# 3-4_TDR.net
KiCad netlist of a schematic drawn in Altium Designer
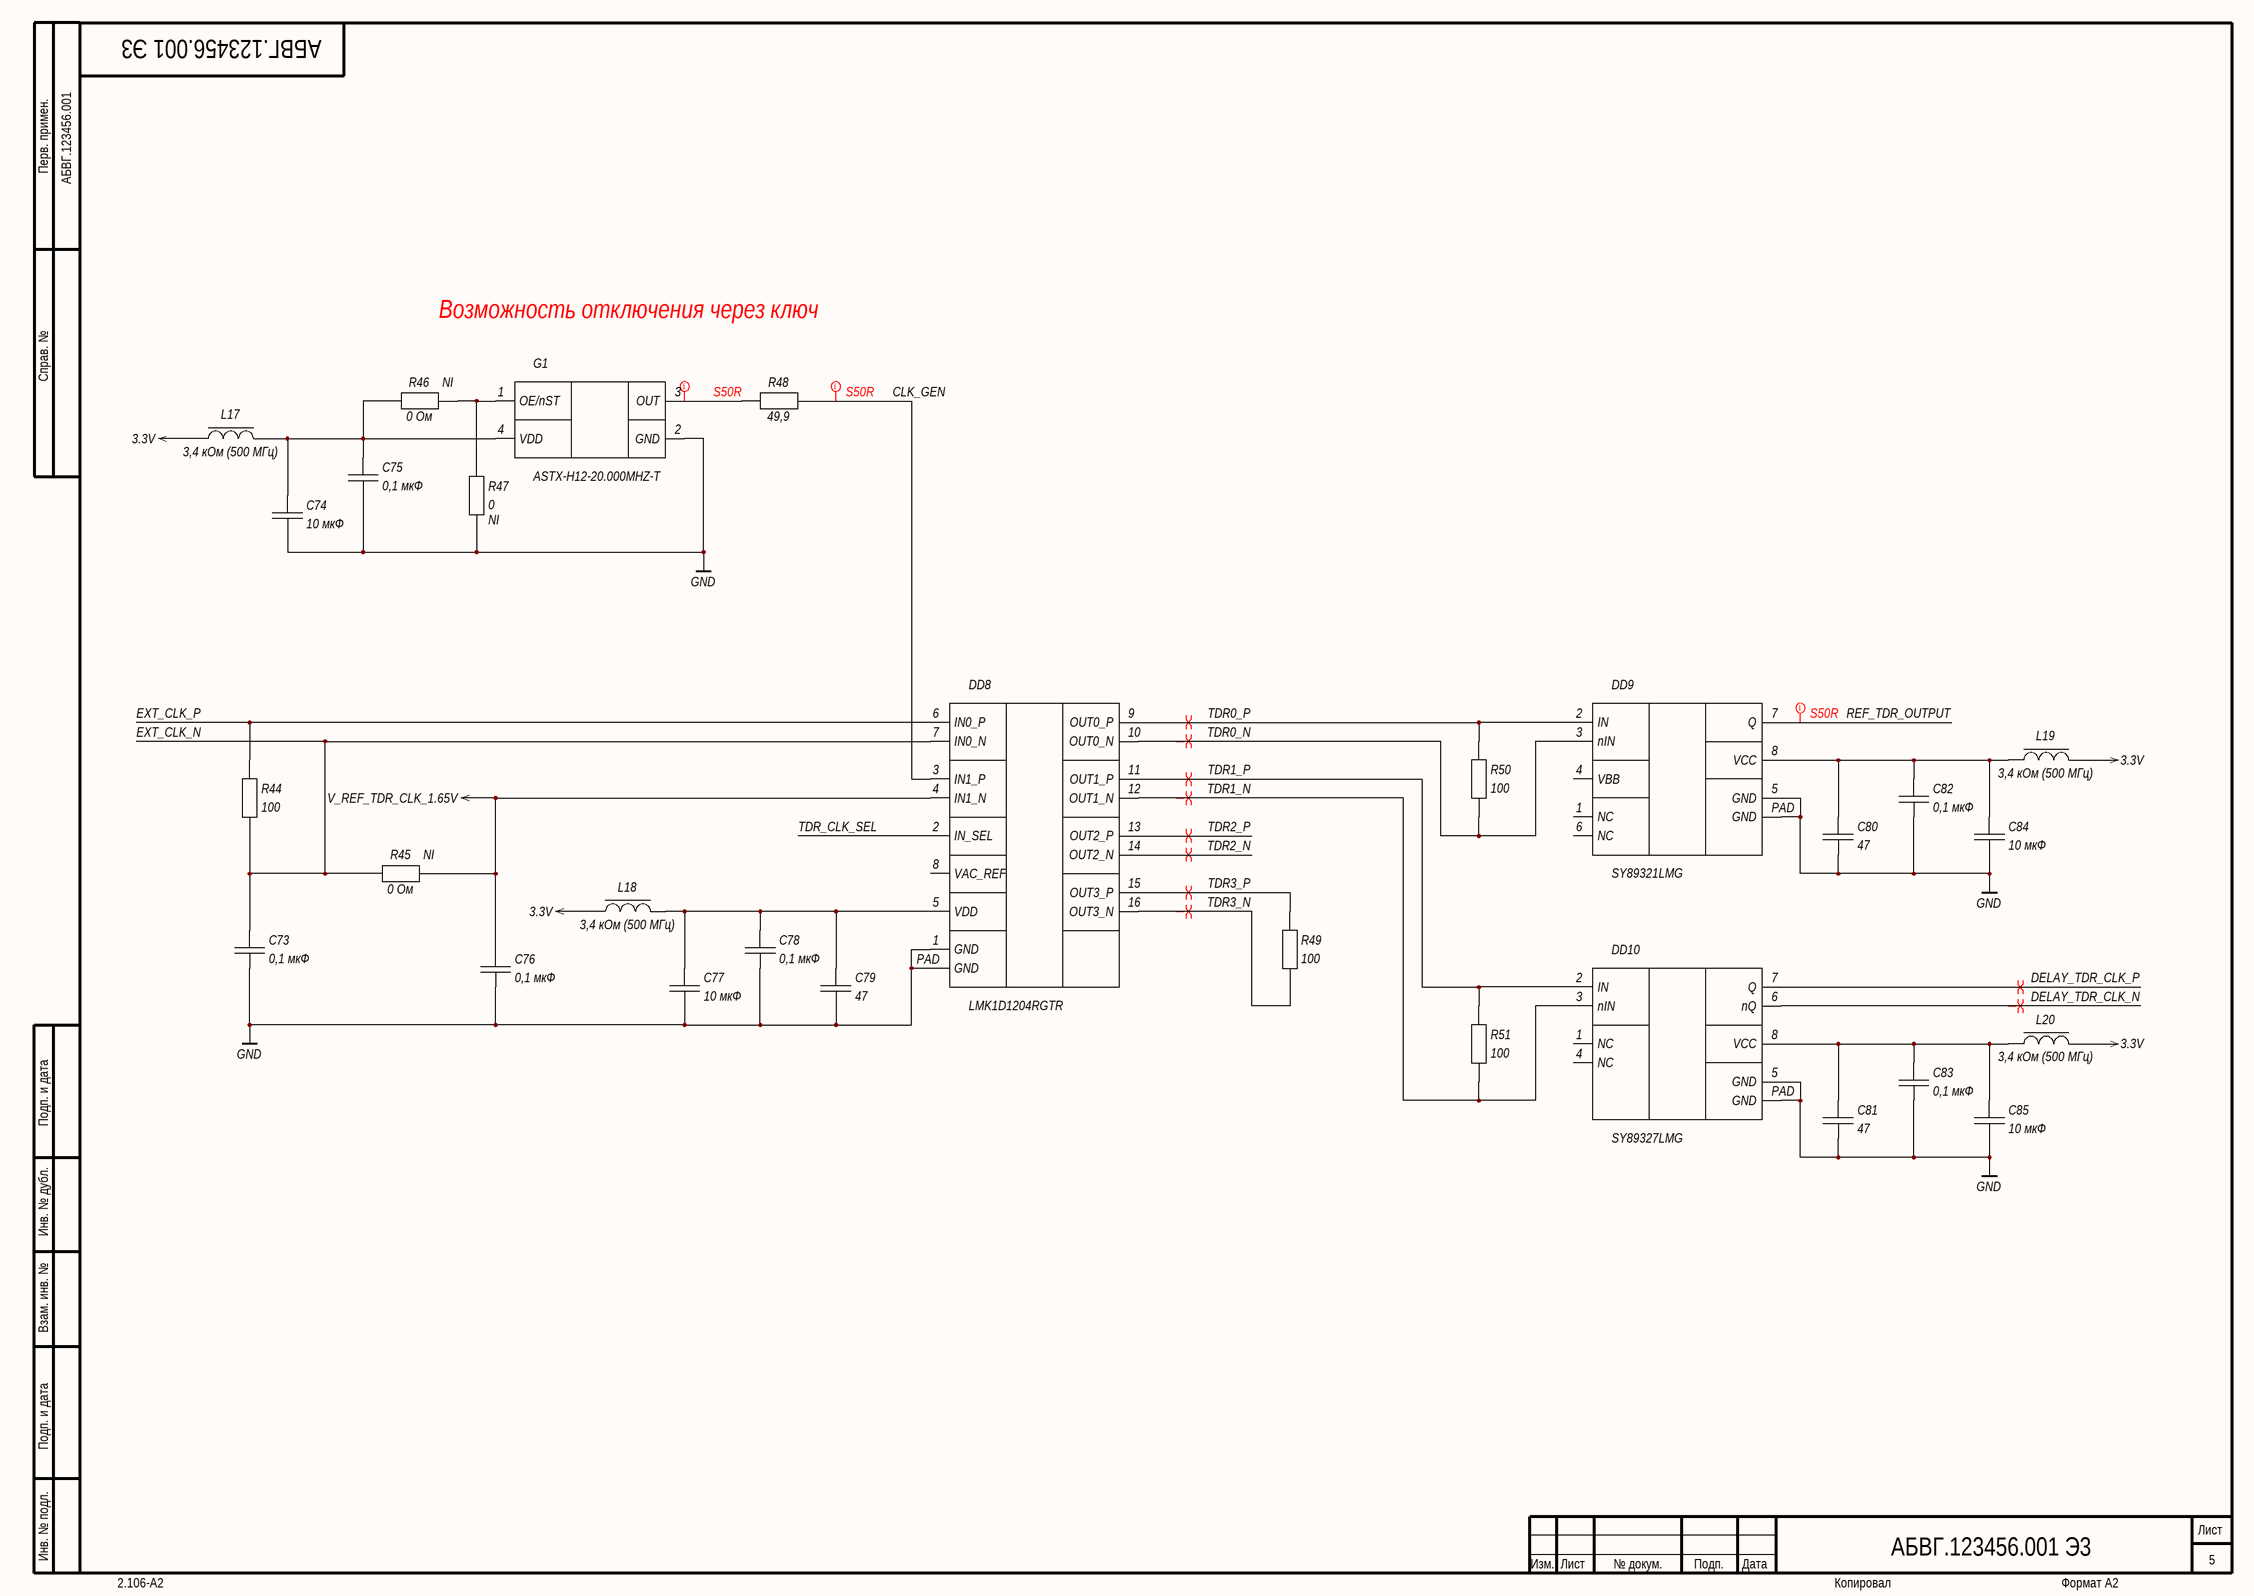
[diagram p0: Э3-4 TDR Делитель.SchDoc]

(export (version "E")
  (design (tool "Eeschema 10.0.6"))
  (components
    (comp (ref "C73")
      (value "0,1 мкФ")
      (footprint "C0402-B-0.5mm")
      (description "0402 X7R 0,1 мкФ ±10 % 50 В")
      (fields (field (name "PARTNUMBER") "GRM155R71H104KE14D"))
      (libsource (lib "Capacitors") (part "Non Polar Ver."))
    )
    (comp (ref "C74")
      (value "10 мкФ")
      (footprint "C0603-B-0.8mm")
      (description "0603 X5R 10 мкФ ±20 % 25 В")
      (fields (field (name "PARTNUMBER") "GRM188R61E106MA73"))
      (libsource (lib "Capacitors") (part "Non Polar Ver."))
    )
    (comp (ref "C75")
      (value "0,1 мкФ")
      (footprint "C0402-B-0.5mm")
      (description "0402 X7R 0,1 мкФ ±10 % 50 В")
      (fields (field (name "PARTNUMBER") "GRM155R71H104KE14D"))
      (libsource (lib "Capacitors") (part "Non Polar Ver."))
    )
    (comp (ref "C76")
      (value "0,1 мкФ")
      (footprint "C0402-B-0.5mm")
      (description "0402 X7R 0,1 мкФ ±10 % 50 В")
      (fields (field (name "PARTNUMBER") "GRM155R71H104KE14D"))
      (libsource (lib "Capacitors") (part "Non Polar Ver."))
    )
    (comp (ref "C77")
      (value "10 мкФ")
      (footprint "C0603-B-0.8mm")
      (description "0603 X5R 10 мкФ ±20 % 25 В")
      (fields (field (name "PARTNUMBER") "GRM188R61E106MA73"))
      (libsource (lib "Capacitors") (part "Non Polar Ver."))
    )
    (comp (ref "C78")
      (value "0,1 мкФ")
      (footprint "C0402-B-0.5mm")
      (description "0402 X7R 0,1 мкФ ±10 % 50 В")
      (fields (field (name "PARTNUMBER") "GRM155R71H104KE14D"))
      (libsource (lib "Capacitors") (part "Non Polar Ver."))
    )
    (comp (ref "C79")
      (value "47")
      (footprint "C0402-B-0.5mm")
      (description "0402 NP0 47 пФ ±5 % 50 В")
      (fields (field (name "PARTNUMBER") "GCM1555C1H470JA16"))
      (libsource (lib "Capacitors") (part "Non Polar Ver."))
    )
    (comp (ref "C80")
      (value "47")
      (footprint "C0402-B-0.5mm")
      (description "0402 NP0 47 пФ ±5 % 50 В")
      (fields (field (name "PARTNUMBER") "GCM1555C1H470JA16"))
      (libsource (lib "Capacitors") (part "Non Polar Ver."))
    )
    (comp (ref "C81")
      (value "47")
      (footprint "C0402-B-0.5mm")
      (description "0402 NP0 47 пФ ±5 % 50 В")
      (fields (field (name "PARTNUMBER") "GCM1555C1H470JA16"))
      (libsource (lib "Capacitors") (part "Non Polar Ver."))
    )
    (comp (ref "C82")
      (value "0,1 мкФ")
      (footprint "C0402-B-0.5mm")
      (description "0402 X7R 0,1 мкФ ±10 % 50 В")
      (fields (field (name "PARTNUMBER") "GRM155R71H104KE14D"))
      (libsource (lib "Capacitors") (part "Non Polar Ver."))
    )
    (comp (ref "C83")
      (value "0,1 мкФ")
      (footprint "C0402-B-0.5mm")
      (description "0402 X7R 0,1 мкФ ±10 % 50 В")
      (fields (field (name "PARTNUMBER") "GRM155R71H104KE14D"))
      (libsource (lib "Capacitors") (part "Non Polar Ver."))
    )
    (comp (ref "C84")
      (value "10 мкФ")
      (footprint "C0603-B-0.8mm")
      (description "0603 X5R 10 мкФ ±20 % 25 В")
      (fields (field (name "PARTNUMBER") "GRM188R61E106MA73"))
      (libsource (lib "Capacitors") (part "Non Polar Ver."))
    )
    (comp (ref "C85")
      (value "10 мкФ")
      (footprint "C0603-B-0.8mm")
      (description "0603 X5R 10 мкФ ±20 % 25 В")
      (fields (field (name "PARTNUMBER") "GRM188R61E106MA73"))
      (libsource (lib "Capacitors") (part "Non Polar Ver."))
    )
    (comp (ref "DD8")
      (value "LMK1D1204RGTR")
      (footprint "16-QFN-3-H1-EP1.7")
      (description "Low Additive Jitter LVDS Buffer")
      (fields (field (name "MANUFACTURER") "Texas Instruments, Inc."))
      (libsource (lib "Digital") (part "LMK1D1204"))
    )
    (comp (ref "DD9")
      (value "SY89321LMG")
      (footprint "8-MLF")
      (description "3.3V DIFFERENTIAL LVPECL/CML/LVDS-to-LVTTL TRANSLATOR")
      (fields (field (name "MANUFACTURER") "Microchip Technology"))
      (libsource (lib "Digital") (part "SY89321L"))
    )
    (comp (ref "DD10")
      (value "SY89327LMG")
      (footprint "8-MLF")
      (description "3.3V 2.5Gbps ANY INPUT-to-LVPECL DIFFERENTIAL TRANSLATOR")
      (fields (field (name "MANUFACTURER") "Microchip Technology"))
      (libsource (lib "Digital") (part "SY89327L"))
    )
    (comp (ref "G1")
      (value "ASTX-H12-20.000MHZ-T")
      (footprint "ASTX-H12")
      (fields (field (name "TOLERANCE") "± ppm"))
      (libsource (lib "Oscilators") (part "Generator"))
    )
    (comp (ref "L17")
      (value "3,4 кОм (500 МГц)")
      (footprint "L0402-B-0.5mm")
      (fields (field (name "PARTNUMBER") "BLM15HD182BH1"))
      (libsource (lib "Inductors") (part "Inductor MC Hor."))
    )
    (comp (ref "L18")
      (value "3,4 кОм (500 МГц)")
      (footprint "L0402-B-0.5mm")
      (fields (field (name "PARTNUMBER") "BLM15HD182BH1"))
      (libsource (lib "Inductors") (part "Inductor MC Hor."))
    )
    (comp (ref "L19")
      (value "3,4 кОм (500 МГц)")
      (footprint "L0402-B-0.5mm")
      (fields (field (name "PARTNUMBER") "BLM15HD182BH1"))
      (libsource (lib "Inductors") (part "Inductor MC Hor."))
    )
    (comp (ref "L20")
      (value "3,4 кОм (500 МГц)")
      (footprint "L0402-B-0.5mm")
      (fields (field (name "PARTNUMBER") "BLM15HD182BH1"))
      (libsource (lib "Inductors") (part "Inductor MC Hor."))
    )
    (comp (ref "R44")
      (value "100")
      (footprint "CR0402-B-0.35mm")
      (description "0402 100 Ом ±1 %")
      (libsource (lib "Resistors") (part "Resistor Ver."))
    )
    (comp (ref "R45")
      (value "0 Ом")
      (footprint "CR0402-B-0.35mm")
      (description "0402 0 Ом")
      (fields (field (name "COMPONENTTYPE") "NI"))
      (libsource (lib "Resistors") (part "Resistor Hor."))
    )
    (comp (ref "R46")
      (value "0 Ом")
      (footprint "CR0402-B-0.35mm")
      (description "0402 0 Ом")
      (fields (field (name "COMPONENTTYPE") "NI"))
      (libsource (lib "Resistors") (part "Resistor Hor."))
    )
    (comp (ref "R47")
      (value "0")
      (footprint "CR0402-B-0.35mm")
      (description "0402 0 Ом")
      (fields (field (name "COMPONENTTYPE") "NI"))
      (libsource (lib "Resistors") (part "Resistor Ver."))
    )
    (comp (ref "R48")
      (value "49,9")
      (footprint "CR0402-B-0.35mm")
      (description "0402 49,9 Ом ±1 %")
      (libsource (lib "Resistors") (part "Resistor Hor."))
    )
    (comp (ref "R49")
      (value "100")
      (footprint "CR0402-B-0.35mm")
      (description "0402 100 Ом ±1 %")
      (libsource (lib "Resistors") (part "Resistor Ver."))
    )
    (comp (ref "R50")
      (value "100")
      (footprint "CR0402-B-0.35mm")
      (description "0402 100 Ом ±1 %")
      (libsource (lib "Resistors") (part "Resistor Ver."))
    )
    (comp (ref "R51")
      (value "100")
      (footprint "CR0402-B-0.35mm")
      (description "0402 100 Ом ±1 %")
      (libsource (lib "Resistors") (part "Resistor Ver."))
    )
  )
  (nets
    (net (code "1") (name "/CLK_GEN") (class "Default")
      (node (ref "DD8") (pin "3") (pinfunction "IN1_P_3") (pintype "passive"))
      (node (ref "R48") (pin "2") (pinfunction "2_2") (pintype "passive"))
    )
    (net (code "2") (name "/DELAY_TDR_CLK_N") (class "Default")
      (node (ref "DD10") (pin "6") (pinfunction "nQ_6") (pintype "passive"))
    )
    (net (code "3") (name "/DELAY_TDR_CLK_P") (class "Default")
      (node (ref "DD10") (pin "7") (pinfunction "Q_7") (pintype "passive"))
    )
    (net (code "4") (name "/EXT_CLK_N") (class "Default")
      (node (ref "C73") (pin "1") (pinfunction "1_1") (pintype "passive"))
      (node (ref "DD8") (pin "7") (pinfunction "IN0_N_7") (pintype "passive"))
      (node (ref "R44") (pin "2") (pinfunction "2_2") (pintype "passive"))
      (node (ref "R45") (pin "1") (pinfunction "1_1") (pintype "passive"))
    )
    (net (code "5") (name "/EXT_CLK_P") (class "Default")
      (node (ref "DD8") (pin "6") (pinfunction "IN0_P_6") (pintype "passive"))
      (node (ref "R44") (pin "1") (pinfunction "1_1") (pintype "passive"))
    )
    (net (code "6") (name "/REF_TDR_OUTPUT") (class "Default")
      (node (ref "DD9") (pin "7") (pinfunction "Q_7") (pintype "passive"))
    )
    (net (code "7") (name "/TDR0_N") (class "Default")
      (node (ref "DD8") (pin "10") (pinfunction "OUT0_N_10") (pintype "passive"))
      (node (ref "DD9") (pin "3") (pinfunction "nIN_3") (pintype "passive"))
      (node (ref "R50") (pin "2") (pinfunction "2_2") (pintype "passive"))
    )
    (net (code "8") (name "/TDR0_P") (class "Default")
      (node (ref "DD8") (pin "9") (pinfunction "OUT0_P_9") (pintype "passive"))
      (node (ref "DD9") (pin "2") (pinfunction "IN_2") (pintype "passive"))
      (node (ref "R50") (pin "1") (pinfunction "1_1") (pintype "passive"))
    )
    (net (code "9") (name "/TDR1_N") (class "Default")
      (node (ref "DD10") (pin "3") (pinfunction "nIN_3") (pintype "passive"))
      (node (ref "DD8") (pin "12") (pinfunction "OUT1_N_12") (pintype "passive"))
      (node (ref "R51") (pin "2") (pinfunction "2_2") (pintype "passive"))
    )
    (net (code "10") (name "/TDR1_P") (class "Default")
      (node (ref "DD10") (pin "2") (pinfunction "IN_2") (pintype "passive"))
      (node (ref "DD8") (pin "11") (pinfunction "OUT1_P_11") (pintype "passive"))
      (node (ref "R51") (pin "1") (pinfunction "1_1") (pintype "passive"))
    )
    (net (code "11") (name "/TDR2_N") (class "Default")
      (node (ref "DD8") (pin "14") (pinfunction "OUT2_N_14") (pintype "passive"))
    )
    (net (code "12") (name "/TDR2_P") (class "Default")
      (node (ref "DD8") (pin "13") (pinfunction "OUT2_P_13") (pintype "passive"))
    )
    (net (code "13") (name "/TDR3_N") (class "Default")
      (node (ref "DD8") (pin "16") (pinfunction "OUT3_N_16") (pintype "passive"))
      (node (ref "R49") (pin "2") (pinfunction "2_2") (pintype "passive"))
    )
    (net (code "14") (name "/TDR3_P") (class "Default")
      (node (ref "DD8") (pin "15") (pinfunction "OUT3_P_15") (pintype "passive"))
      (node (ref "R49") (pin "1") (pinfunction "1_1") (pintype "passive"))
    )
    (net (code "15") (name "/TDR_CLK_SEL") (class "Default")
      (node (ref "DD8") (pin "2") (pinfunction "IN_SEL_2") (pintype "passive"))
    )
    (net (code "16") (name "3.3V") (class "Default")
      (node (ref "L17") (pin "1") (pinfunction "1_1") (pintype "passive"))
      (node (ref "L18") (pin "1") (pinfunction "1_1") (pintype "passive"))
      (node (ref "L19") (pin "2") (pinfunction "2_2") (pintype "passive"))
      (node (ref "L20") (pin "2") (pinfunction "2_2") (pintype "passive"))
    )
    (net (code "17") (name "GND") (class "Default")
      (node (ref "C73") (pin "2") (pinfunction "2_2") (pintype "passive"))
      (node (ref "C74") (pin "2") (pinfunction "2_2") (pintype "passive"))
      (node (ref "C75") (pin "2") (pinfunction "2_2") (pintype "passive"))
      (node (ref "C76") (pin "2") (pinfunction "2_2") (pintype "passive"))
      (node (ref "C77") (pin "2") (pinfunction "2_2") (pintype "passive"))
      (node (ref "C78") (pin "2") (pinfunction "2_2") (pintype "passive"))
      (node (ref "C79") (pin "2") (pinfunction "2_2") (pintype "passive"))
      (node (ref "C80") (pin "2") (pinfunction "2_2") (pintype "passive"))
      (node (ref "C81") (pin "2") (pinfunction "2_2") (pintype "passive"))
      (node (ref "C82") (pin "2") (pinfunction "2_2") (pintype "passive"))
      (node (ref "C83") (pin "2") (pinfunction "2_2") (pintype "passive"))
      (node (ref "C84") (pin "2") (pinfunction "2_2") (pintype "passive"))
      (node (ref "C85") (pin "2") (pinfunction "2_2") (pintype "passive"))
      (node (ref "DD10") (pin "5") (pinfunction "GND_5") (pintype "passive"))
      (node (ref "DD10") (pin "PAD") (pinfunction "GND_PAD") (pintype "passive"))
      (node (ref "DD8") (pin "1") (pinfunction "GND_1") (pintype "passive"))
      (node (ref "DD8") (pin "PAD") (pinfunction "GND_PAD") (pintype "passive"))
      (node (ref "DD9") (pin "5") (pinfunction "GND_5") (pintype "passive"))
      (node (ref "DD9") (pin "PAD") (pinfunction "GND_PAD") (pintype "passive"))
      (node (ref "G1") (pin "2") (pinfunction "GND_2") (pintype "passive"))
      (node (ref "R47") (pin "2") (pinfunction "2_2") (pintype "passive"))
    )
    (net (code "18") (name "Net-(DD8-VDD)") (class "Default")
      (node (ref "C77") (pin "1") (pinfunction "1_1") (pintype "passive"))
      (node (ref "C78") (pin "1") (pinfunction "1_1") (pintype "passive"))
      (node (ref "C79") (pin "1") (pinfunction "1_1") (pintype "passive"))
      (node (ref "DD8") (pin "5") (pinfunction "VDD_5") (pintype "passive"))
      (node (ref "L18") (pin "2") (pinfunction "2_2") (pintype "passive"))
    )
    (net (code "19") (name "Net-(DD9-VCC)") (class "Default")
      (node (ref "C80") (pin "1") (pinfunction "1_1") (pintype "passive"))
      (node (ref "C82") (pin "1") (pinfunction "1_1") (pintype "passive"))
      (node (ref "C84") (pin "1") (pinfunction "1_1") (pintype "passive"))
      (node (ref "DD9") (pin "8") (pinfunction "VCC_8") (pintype "passive"))
      (node (ref "L19") (pin "1") (pinfunction "1_1") (pintype "passive"))
    )
    (net (code "20") (name "Net-(DD10-VCC)") (class "Default")
      (node (ref "C81") (pin "1") (pinfunction "1_1") (pintype "passive"))
      (node (ref "C83") (pin "1") (pinfunction "1_1") (pintype "passive"))
      (node (ref "C85") (pin "1") (pinfunction "1_1") (pintype "passive"))
      (node (ref "DD10") (pin "8") (pinfunction "VCC_8") (pintype "passive"))
      (node (ref "L20") (pin "1") (pinfunction "1_1") (pintype "passive"))
    )
    (net (code "21") (name "Net-(G1-OE{slash}nST)") (class "Default")
      (node (ref "G1") (pin "1") (pinfunction "OE/nST_1") (pintype "passive"))
      (node (ref "R46") (pin "2") (pinfunction "2_2") (pintype "passive"))
      (node (ref "R47") (pin "1") (pinfunction "1_1") (pintype "passive"))
    )
    (net (code "22") (name "Net-(G1-OUT)") (class "Default")
      (node (ref "G1") (pin "3") (pinfunction "OUT_3") (pintype "passive"))
      (node (ref "R48") (pin "1") (pinfunction "1_1") (pintype "passive"))
    )
    (net (code "23") (name "Net-(G1-VDD)") (class "Default")
      (node (ref "C74") (pin "1") (pinfunction "1_1") (pintype "passive"))
      (node (ref "C75") (pin "1") (pinfunction "1_1") (pintype "passive"))
      (node (ref "G1") (pin "4") (pinfunction "VDD_4") (pintype "passive"))
      (node (ref "L17") (pin "2") (pinfunction "2_2") (pintype "passive"))
      (node (ref "R46") (pin "1") (pinfunction "1_1") (pintype "passive"))
    )
    (net (code "24") (name "V_REF_TDR_CLK_1.65V") (class "Default")
      (node (ref "C76") (pin "1") (pinfunction "1_1") (pintype "passive"))
      (node (ref "DD8") (pin "4") (pinfunction "IN1_N_4") (pintype "passive"))
      (node (ref "R45") (pin "2") (pinfunction "2_2") (pintype "passive"))
    )
    (net (code "25") (name "unconnected-(DD8-VAC_REF-Pad8)") (class "Default")
      (node (ref "DD8") (pin "8") (pinfunction "VAC_REF_8") (pintype "passive"))
    )
    (net (code "26") (name "unconnected-(DD9-NC-Pad1)") (class "Default")
      (node (ref "DD9") (pin "1") (pinfunction "NC_1") (pintype "passive"))
    )
    (net (code "27") (name "unconnected-(DD9-NC-Pad6)") (class "Default")
      (node (ref "DD9") (pin "6") (pinfunction "NC_6") (pintype "passive"))
    )
    (net (code "28") (name "unconnected-(DD9-VBB-Pad4)") (class "Default")
      (node (ref "DD9") (pin "4") (pinfunction "VBB_4") (pintype "passive"))
    )
    (net (code "29") (name "unconnected-(DD10-NC-Pad1)") (class "Default")
      (node (ref "DD10") (pin "1") (pinfunction "NC_1") (pintype "passive"))
    )
    (net (code "30") (name "unconnected-(DD10-NC-Pad4)") (class "Default")
      (node (ref "DD10") (pin "4") (pinfunction "NC_4") (pintype "passive"))
    )
  )
)
